# SH6_-_LOAD_MONITORING_2.net
KiCad netlist of a schematic drawn in Altium Designer
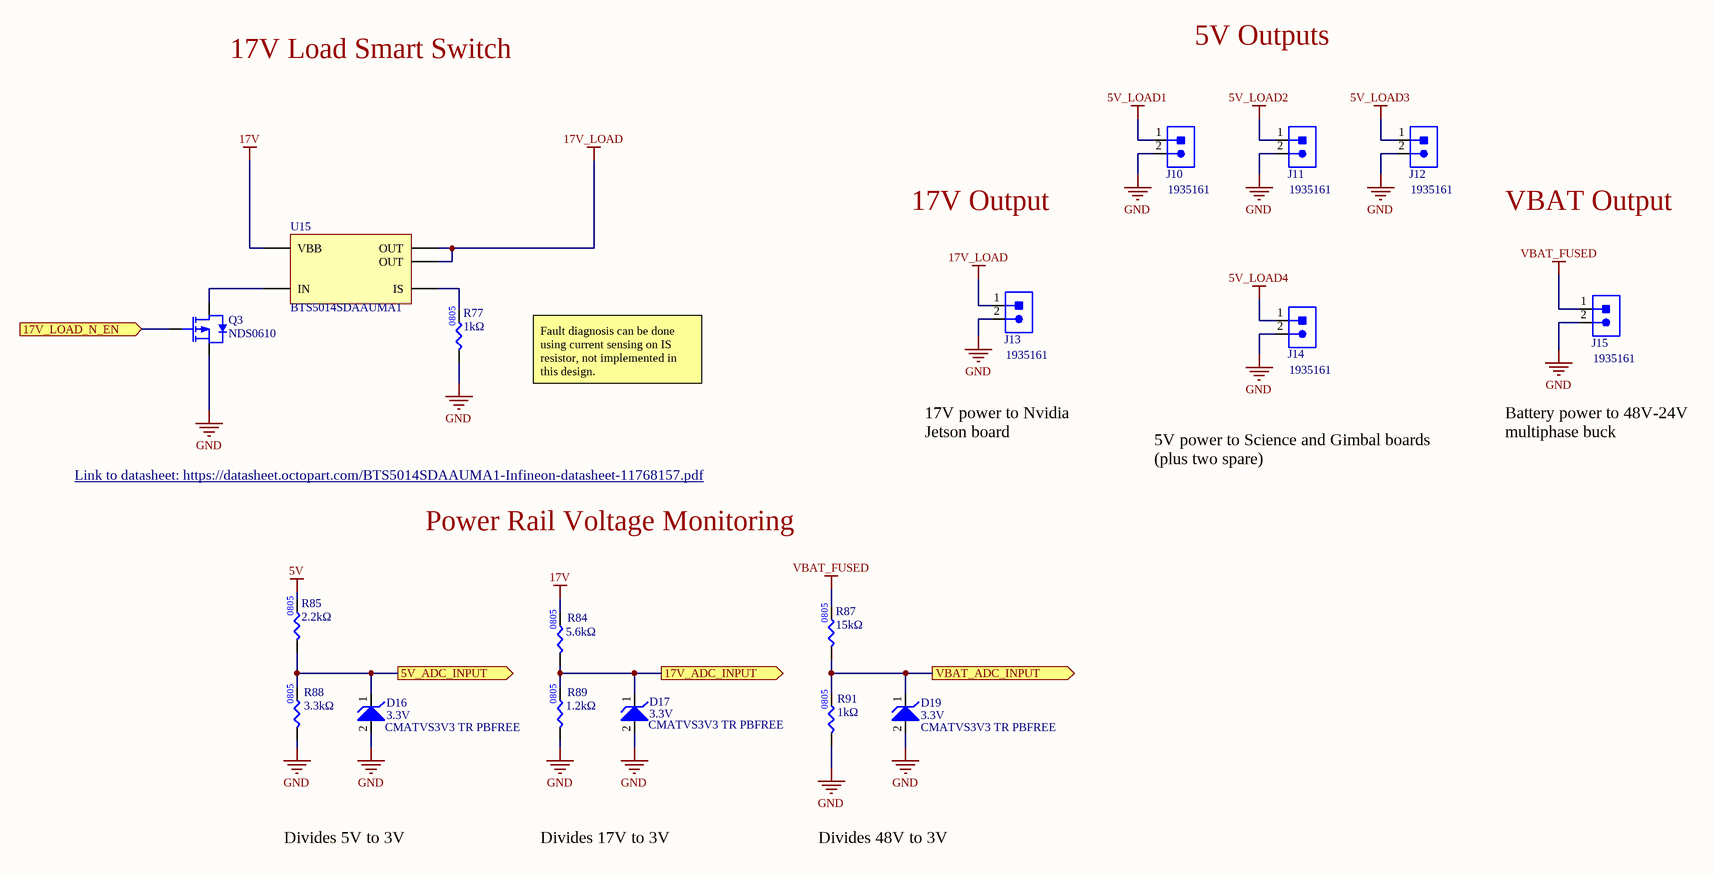
[diagram p0: SH6 - LOAD MONITORING 2.SchDoc]

(export (version "E")
  (design (tool "Eeschema 10.0.6"))
  (components
    (comp (ref "D16")
      (value "TVS_DIODE_UNIDIR_3.3V_7A")
      (footprint "SOD-923")
      (description "TVS DIODE 3.3VWM 11VC SOD923")
      (fields
        (field (name "MANUFACTURER PART NUMBER 1") "CMATVS3V3 TR PBFREE")
        (field (name "VOLTAGE - REVERSE STANDOFF (TYP)") "3.3V")
      )
      (libsource (lib "UWRT_Schematic_Library_2020") (part "TVS_DIODE_UNIDIR_3.3V_7A"))
    )
    (comp (ref "D17")
      (value "TVS_DIODE_UNIDIR_3.3V_7A")
      (footprint "SOD-923")
      (description "TVS DIODE 3.3VWM 11VC SOD923")
      (fields
        (field (name "MANUFACTURER PART NUMBER 1") "CMATVS3V3 TR PBFREE")
        (field (name "VOLTAGE - REVERSE STANDOFF (TYP)") "3.3V")
      )
      (libsource (lib "UWRT_Schematic_Library_2020") (part "TVS_DIODE_UNIDIR_3.3V_7A"))
    )
    (comp (ref "D19")
      (value "TVS_DIODE_UNIDIR_3.3V_7A")
      (footprint "SOD-923")
      (description "TVS DIODE 3.3VWM 11VC SOD923")
      (fields
        (field (name "MANUFACTURER PART NUMBER 1") "CMATVS3V3 TR PBFREE")
        (field (name "VOLTAGE - REVERSE STANDOFF (TYP)") "3.3V")
      )
      (libsource (lib "UWRT_Schematic_Library_2020") (part "TVS_DIODE_UNIDIR_3.3V_7A"))
    )
    (comp (ref "J10")
      (value "CON_2M_TERM")
      (footprint "1935161")
      (description "TERM BLK 2POS SIDE ENTRY 5MM")
      (fields (field (name "VOLTAGE") "300V") (field (name "MANUFACTURER PART NUMBER 1") "1935161"))
      (libsource (lib "UWRT_Schematic_Library_2020") (part "CON_2M_TERM"))
    )
    (comp (ref "J11")
      (value "CON_2M_TERM")
      (footprint "1935161")
      (description "TERM BLK 2POS SIDE ENTRY 5MM")
      (fields (field (name "VOLTAGE") "300V") (field (name "MANUFACTURER PART NUMBER 1") "1935161"))
      (libsource (lib "UWRT_Schematic_Library_2020") (part "CON_2M_TERM"))
    )
    (comp (ref "J12")
      (value "CON_2M_TERM")
      (footprint "1935161")
      (description "TERM BLK 2POS SIDE ENTRY 5MM")
      (fields (field (name "VOLTAGE") "300V") (field (name "MANUFACTURER PART NUMBER 1") "1935161"))
      (libsource (lib "UWRT_Schematic_Library_2020") (part "CON_2M_TERM"))
    )
    (comp (ref "J13")
      (value "CON_2M_TERM")
      (footprint "1935161")
      (description "TERM BLK 2POS SIDE ENTRY 5MM")
      (fields (field (name "VOLTAGE") "300V") (field (name "MANUFACTURER PART NUMBER 1") "1935161"))
      (libsource (lib "UWRT_Schematic_Library_2020") (part "CON_2M_TERM"))
    )
    (comp (ref "J14")
      (value "CON_2M_TERM")
      (footprint "1935161")
      (description "TERM BLK 2POS SIDE ENTRY 5MM")
      (fields (field (name "VOLTAGE") "300V") (field (name "MANUFACTURER PART NUMBER 1") "1935161"))
      (libsource (lib "UWRT_Schematic_Library_2020") (part "CON_2M_TERM"))
    )
    (comp (ref "J15")
      (value "CON_2M_TERM")
      (footprint "1935161")
      (description "TERM BLK 2POS SIDE ENTRY 5MM")
      (fields (field (name "VOLTAGE") "300V") (field (name "MANUFACTURER PART NUMBER 1") "1935161"))
      (libsource (lib "UWRT_Schematic_Library_2020") (part "CON_2M_TERM"))
    )
    (comp (ref "Q3")
      (value "PMOS_60V_120mA")
      (footprint "SOT23-3")
      (description "MOSFET P-CH 60V 120MA SOT-23")
      (fields (field (name "MANUFACTURER PART NUMBER 1") "NDS0610"))
      (libsource (lib "UWRT_Schematic_Library_2020") (part "PMOS_60V_120mA"))
    )
    (comp (ref "R77")
      (value "1kΩ")
      (footprint "RES0805")
      (description "RES 1K OHM 1% 1/8W 0805")
      (fields (field (name "LCSC PART #") "C17513") (field (name "Comment") "RES_1kΩ_0805_1%"))
      (libsource (lib "UWRT_Schematic_Library_2020") (part "RES_1kΩ_0805_1%"))
    )
    (comp (ref "R84")
      (value "5.6kΩ")
      (footprint "RES0805")
      (description "RES 5.6K OHM 5% 1/8W 0805")
      (fields (field (name "TOLERANCE") "5%") (field (name "Comment") "RES_5.6kΩ_0805"))
      (libsource (lib "UWRT_Schematic_Library_2020") (part "RES_5.6kΩ_0805_5%"))
    )
    (comp (ref "R85")
      (value "2.2kΩ")
      (footprint "RES0805")
      (description "RES 2.2K OHM 5% 1/8W 0805")
      (fields (field (name "TOLERANCE") "5%") (field (name "Comment") "RES_2.2kΩ_0805"))
      (libsource (lib "UWRT_Schematic_Library_2020") (part "RES_2.2kΩ_0805_5%"))
    )
    (comp (ref "R87")
      (value "15kΩ")
      (footprint "RES0805")
      (description "RES 15K OHM 1% 1/8W 0805")
      (fields (field (name "Comment") "RES_15kΩ_0805_1%"))
      (libsource (lib "UWRT_Schematic_Library_2020") (part "RES_15kΩ_0805_1%"))
    )
    (comp (ref "R88")
      (value "3.3kΩ")
      (footprint "RES0805")
      (description "RES 3.3K OHM 1% 1/8W 0805")
      (fields (field (name "LCSC PART #") "C26010") (field (name "Comment") "RES_3.3kΩ_0805_1%"))
      (libsource (lib "UWRT_Schematic_Library_2020") (part "RES_3.3kΩ_0805_1%"))
    )
    (comp (ref "R89")
      (value "1.2kΩ")
      (footprint "RES0805")
      (description "RES 1.2K OHM 5% 1/8W 0805")
      (fields (field (name "TOLERANCE") "5%") (field (name "Comment") "RES_1.2kΩ_0805"))
      (libsource (lib "UWRT_Schematic_Library_2020") (part "RES_1.2kΩ_0805_5%"))
    )
    (comp (ref "R91")
      (value "1kΩ")
      (footprint "RES0805")
      (description "RES 1K OHM 1% 1/8W 0805")
      (fields (field (name "LCSC PART #") "C17513") (field (name "Comment") "RES_1kΩ_0805_1%_1"))
      (libsource (lib "UWRT_Schematic_Library_2020") (part "RES_1kΩ_0805_1%_1"))
    )
    (comp (ref "U15")
      (value "BTS5014SDAAUMA1")
      (footprint "D2PAK-4")
      (description "IC PWR SWITCH N-CHAN 1:1 TO252-5")
      (fields (field (name "MANUFACTURER PART NUMBER 1") "BTS5014SDAAUMA1"))
      (libsource (lib "UWRT_Schematic_Library_2020") (part "BTS5014SDAAUMA1"))
    )
  )
  (nets
    (net (code "1") (name "/5V_ADC_INPUT") (class "Default")
      (node (ref "D16") (pin "1") (pinfunction "1_1") (pintype "passive"))
      (node (ref "R85") (pin "1") (pinfunction "1_1") (pintype "passive"))
      (node (ref "R88") (pin "2") (pinfunction "2_2") (pintype "passive"))
    )
    (net (code "2") (name "/17V_ADC_INPUT") (class "Default")
      (node (ref "D17") (pin "1") (pinfunction "1_1") (pintype "passive"))
      (node (ref "R84") (pin "1") (pinfunction "1_1") (pintype "passive"))
      (node (ref "R89") (pin "2") (pinfunction "2_2") (pintype "passive"))
    )
    (net (code "3") (name "/17V_LOAD_N_EN") (class "Default")
      (node (ref "Q3") (pin "1") (pinfunction "Gate_1") (pintype "passive"))
    )
    (net (code "4") (name "/VBAT_ADC_INPUT") (class "Default")
      (node (ref "D19") (pin "1") (pinfunction "1_1") (pintype "passive"))
      (node (ref "R87") (pin "1") (pinfunction "1_1") (pintype "passive"))
      (node (ref "R91") (pin "2") (pinfunction "2_2") (pintype "passive"))
    )
    (net (code "5") (name "5V") (class "Default")
      (node (ref "R85") (pin "2") (pinfunction "2_2") (pintype "passive"))
    )
    (net (code "6") (name "5V_LOAD1") (class "Default")
      (node (ref "J10") (pin "1") (pinfunction "1_1") (pintype "passive"))
    )
    (net (code "7") (name "5V_LOAD2") (class "Default")
      (node (ref "J11") (pin "1") (pinfunction "1_1") (pintype "passive"))
    )
    (net (code "8") (name "5V_LOAD3") (class "Default")
      (node (ref "J12") (pin "1") (pinfunction "1_1") (pintype "passive"))
    )
    (net (code "9") (name "5V_LOAD4") (class "Default")
      (node (ref "J14") (pin "1") (pinfunction "1_1") (pintype "passive"))
    )
    (net (code "10") (name "17V") (class "Default")
      (node (ref "R84") (pin "2") (pinfunction "2_2") (pintype "passive"))
      (node (ref "U15") (pin "3") (pinfunction "VBB_3") (pintype "passive"))
    )
    (net (code "11") (name "17V_LOAD") (class "Default")
      (node (ref "J13") (pin "1") (pinfunction "1_1") (pintype "passive"))
      (node (ref "U15") (pin "1") (pinfunction "OUT_1") (pintype "passive"))
      (node (ref "U15") (pin "5") (pinfunction "OUT_5") (pintype "passive"))
    )
    (net (code "12") (name "GND") (class "Default")
      (node (ref "D16") (pin "2") (pinfunction "2_2") (pintype "passive"))
      (node (ref "D17") (pin "2") (pinfunction "2_2") (pintype "passive"))
      (node (ref "D19") (pin "2") (pinfunction "2_2") (pintype "passive"))
      (node (ref "J10") (pin "2") (pinfunction "2_2") (pintype "passive"))
      (node (ref "J11") (pin "2") (pinfunction "2_2") (pintype "passive"))
      (node (ref "J12") (pin "2") (pinfunction "2_2") (pintype "passive"))
      (node (ref "J13") (pin "2") (pinfunction "2_2") (pintype "passive"))
      (node (ref "J14") (pin "2") (pinfunction "2_2") (pintype "passive"))
      (node (ref "J15") (pin "2") (pinfunction "2_2") (pintype "passive"))
      (node (ref "Q3") (pin "2") (pinfunction "Source_2") (pintype "passive"))
      (node (ref "R77") (pin "1") (pinfunction "1_1") (pintype "passive"))
      (node (ref "R88") (pin "1") (pinfunction "1_1") (pintype "passive"))
      (node (ref "R89") (pin "1") (pinfunction "1_1") (pintype "passive"))
      (node (ref "R91") (pin "1") (pinfunction "1_1") (pintype "passive"))
    )
    (net (code "13") (name "Net-(Q3-Drain)") (class "Default")
      (node (ref "Q3") (pin "3") (pinfunction "Drain_3") (pintype "passive"))
      (node (ref "U15") (pin "2") (pinfunction "IN_2") (pintype "passive"))
    )
    (net (code "14") (name "Net-(U15-IS)") (class "Default")
      (node (ref "R77") (pin "2") (pinfunction "2_2") (pintype "passive"))
      (node (ref "U15") (pin "4") (pinfunction "IS_4") (pintype "passive"))
    )
    (net (code "15") (name "VBAT_FUSED") (class "Default")
      (node (ref "J15") (pin "1") (pinfunction "1_1") (pintype "passive"))
      (node (ref "R87") (pin "2") (pinfunction "2_2") (pintype "passive"))
    )
  )
)
